# Test1.net
KiCad netlist of a schematic drawn in Altium Designer
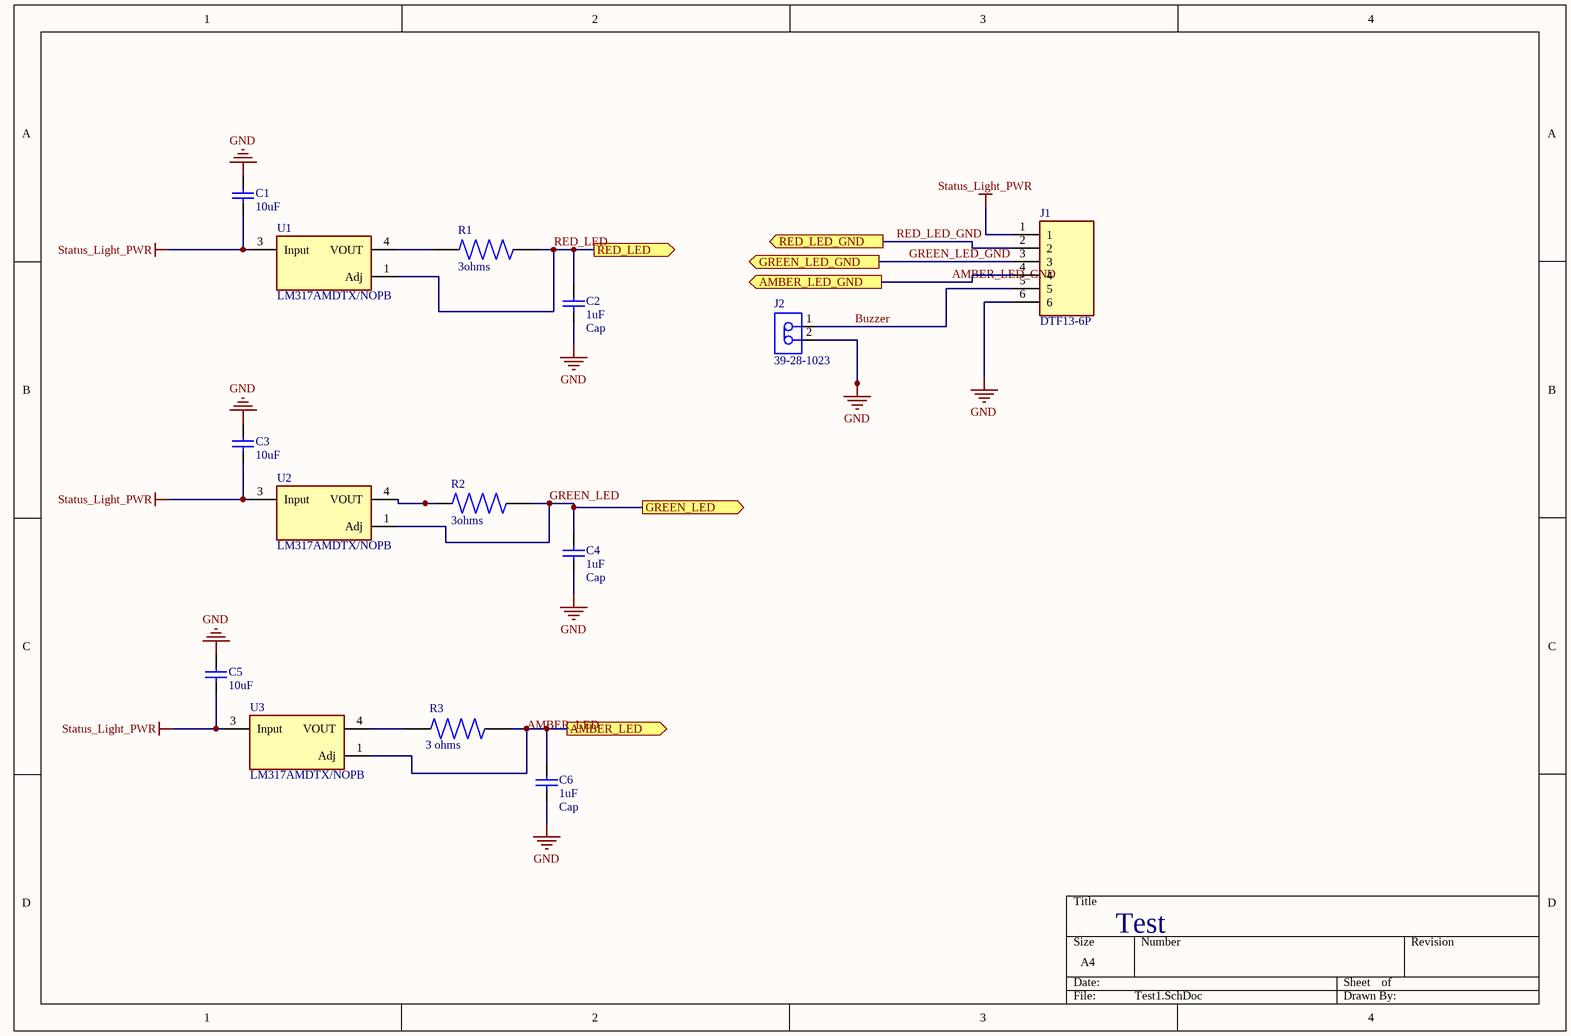
[diagram p0: Test1.SchDoc]

(export (version "E")
  (design (tool "Eeschema 10.0.6"))
  (components
    (comp (ref "C1")
      (value "Cap")
      (footprint "1608[0603]")
      (description "Capacitor")
      (fields (field (name "C2") "10uF") (field (name "PUBLISHER") "Altium Limited"))
      (libsource (lib "Miscellaneous Devices") (part "Cap"))
    )
    (comp (ref "C2")
      (value "Cap")
      (footprint "1608[0603]")
      (description "Capacitor")
      (fields (field (name "C2") "1uF") (field (name "PUBLISHER") "Altium Limited"))
      (libsource (lib "Miscellaneous Devices") (part "Cap"))
    )
    (comp (ref "C3")
      (value "Cap")
      (footprint "1608[0603]")
      (description "Capacitor")
      (fields (field (name "C2") "10uF") (field (name "PUBLISHER") "Altium Limited"))
      (libsource (lib "Miscellaneous Devices") (part "Cap"))
    )
    (comp (ref "C4")
      (value "Cap")
      (footprint "1608[0603]")
      (description "Capacitor")
      (fields (field (name "C2") "1uF") (field (name "PUBLISHER") "Altium Limited"))
      (libsource (lib "Miscellaneous Devices") (part "Cap"))
    )
    (comp (ref "C5")
      (value "Cap")
      (footprint "1608[0603]")
      (description "Capacitor")
      (fields (field (name "C2") "10uF") (field (name "PUBLISHER") "Altium Limited"))
      (libsource (lib "Miscellaneous Devices") (part "Cap"))
    )
    (comp (ref "C6")
      (value "Cap")
      (footprint "1608[0603]")
      (description "Capacitor")
      (fields (field (name "C2") "1uF") (field (name "PUBLISHER") "Altium Limited"))
      (libsource (lib "Miscellaneous Devices") (part "Cap"))
    )
    (comp (ref "J1")
      (value "DTF13-6P")
      (footprint "TE_DTF13-6P")
      (description "Conn Wire to Board RCP 6 POS 4.45mm Solder RA Thru-Hole Automotive Package")
      (fields (field (name "MF") "TE Connectivity"))
      (libsource (lib "DTF13-6P") (part "DTF13-6P"))
    )
    (comp (ref "J2")
      (value "39-28-1023")
      (footprint "MOLX-39-28-1023-2_V")
      (fields (field (name "MANUFACTURER") "Molex"))
      (libsource (lib "Altium Content Vault") (part "CN-2P-F-QF2"))
    )
    (comp (ref "R1")
      (value "3ohms")
      (footprint "RESC3216X70N")
      (fields (field (name "MP") "RMCF1206FT3R00"))
      (libsource (lib "RMCF1206FT3R00") (part "RMCF1206FT3R00"))
    )
    (comp (ref "R2")
      (value "3ohms")
      (footprint "RESC3216X70N")
      (fields (field (name "MP") "RMCF1206FT3R00"))
      (libsource (lib "RMCF1206FT3R00") (part "RMCF1206FT3R00"))
    )
    (comp (ref "R3")
      (value "3 ohms")
      (footprint "RESC3216X70N")
      (fields (field (name "MP") "RMCF1206FT3R00"))
      (libsource (lib "RMCF1206FT3R00") (part "RMCF1206FT3R00"))
    )
    (comp (ref "U1")
      (value "LM317AMDTX/NOPB")
      (footprint "FP-NDP0003B-MFG")
      (description "IC REG LIN POS ADJ 1.5A TO252-3")
      (fields
        (field (name "MANUFACTURER") "Texas Instruments")
        (field (name "OCTOPART") "https://octopart.com/lm317amdtx%2Fnopb-texas+instruments-24813637")
      )
      (libsource (lib "Altium Content Vault") (part "f5e461452ecc37898cb4f29636b01e7"))
    )
    (comp (ref "U2")
      (value "LM317AMDTX/NOPB")
      (footprint "FP-NDP0003B-MFG")
      (description "IC REG LIN POS ADJ 1.5A TO252-3")
      (fields
        (field (name "MANUFACTURER") "Texas Instruments")
        (field (name "OCTOPART") "https://octopart.com/lm317amdtx%2Fnopb-texas+instruments-24813637")
      )
      (libsource (lib "Altium Content Vault") (part "f5e461452ecc37898cb4f29636b01e7"))
    )
    (comp (ref "U3")
      (value "LM317AMDTX/NOPB")
      (footprint "FP-NDP0003B-MFG")
      (description "IC REG LIN POS ADJ 1.5A TO252-3")
      (fields
        (field (name "MANUFACTURER") "Texas Instruments")
        (field (name "OCTOPART") "https://octopart.com/lm317amdtx%2Fnopb-texas+instruments-24813637")
      )
      (libsource (lib "Altium Content Vault") (part "f5e461452ecc37898cb4f29636b01e7"))
    )
  )
  (nets
    (net (code "1") (name "/AMBER_LED") (class "Default")
      (node (ref "C6") (pin "2") (pinfunction "2_2") (pintype "passive"))
      (node (ref "R3") (pin "2") (pinfunction "2_2") (pintype "passive"))
      (node (ref "U3") (pin "1") (pinfunction "Adj_1") (pintype "passive"))
    )
    (net (code "2") (name "/AMBER_LED_GND") (class "Default")
      (node (ref "J1") (pin "4") (pinfunction "4_4") (pintype "passive"))
    )
    (net (code "3") (name "/Buzzer") (class "Default")
      (node (ref "J1") (pin "5") (pinfunction "5_5") (pintype "passive"))
      (node (ref "J2") (pin "1") (pinfunction "1_1") (pintype "passive"))
    )
    (net (code "4") (name "/GREEN_LED") (class "Default")
      (node (ref "C4") (pin "2") (pinfunction "2_2") (pintype "passive"))
      (node (ref "R2") (pin "2") (pinfunction "2_2") (pintype "passive"))
      (node (ref "U2") (pin "1") (pinfunction "Adj_1") (pintype "passive"))
    )
    (net (code "5") (name "/GREEN_LED_GND") (class "Default")
      (node (ref "J1") (pin "3") (pinfunction "3_3") (pintype "passive"))
    )
    (net (code "6") (name "/RED_LED") (class "Default")
      (node (ref "C2") (pin "2") (pinfunction "2_2") (pintype "passive"))
      (node (ref "R1") (pin "2") (pinfunction "2_2") (pintype "passive"))
      (node (ref "U1") (pin "1") (pinfunction "Adj_1") (pintype "passive"))
    )
    (net (code "7") (name "/RED_LED_GND") (class "Default")
      (node (ref "J1") (pin "2") (pinfunction "2_2") (pintype "passive"))
    )
    (net (code "8") (name "GND") (class "Default")
      (node (ref "C1") (pin "2") (pinfunction "2_2") (pintype "passive"))
      (node (ref "C2") (pin "1") (pinfunction "1_1") (pintype "passive"))
      (node (ref "C3") (pin "2") (pinfunction "2_2") (pintype "passive"))
      (node (ref "C4") (pin "1") (pinfunction "1_1") (pintype "passive"))
      (node (ref "C5") (pin "2") (pinfunction "2_2") (pintype "passive"))
      (node (ref "C6") (pin "1") (pinfunction "1_1") (pintype "passive"))
      (node (ref "J1") (pin "6") (pinfunction "6_6") (pintype "passive"))
      (node (ref "J2") (pin "2") (pinfunction "2_2") (pintype "passive"))
    )
    (net (code "9") (name "Net-(U1-VOUT)") (class "Default")
      (node (ref "R1") (pin "1") (pinfunction "1_1") (pintype "passive"))
      (node (ref "U1") (pin "4") (pinfunction "VOUT_4") (pintype "power_in"))
    )
    (net (code "10") (name "Net-(U2-VOUT)") (class "Default")
      (node (ref "R2") (pin "1") (pinfunction "1_1") (pintype "passive"))
      (node (ref "U2") (pin "4") (pinfunction "VOUT_4") (pintype "power_in"))
    )
    (net (code "11") (name "Net-(U3-VOUT)") (class "Default")
      (node (ref "R3") (pin "1") (pinfunction "1_1") (pintype "passive"))
      (node (ref "U3") (pin "4") (pinfunction "VOUT_4") (pintype "power_in"))
    )
    (net (code "12") (name "Status_Light_PWR") (class "Default")
      (node (ref "C1") (pin "1") (pinfunction "1_1") (pintype "passive"))
      (node (ref "C3") (pin "1") (pinfunction "1_1") (pintype "passive"))
      (node (ref "C5") (pin "1") (pinfunction "1_1") (pintype "passive"))
      (node (ref "J1") (pin "1") (pinfunction "1_1") (pintype "passive"))
      (node (ref "U1") (pin "3") (pinfunction "Input_3") (pintype "power_in"))
      (node (ref "U2") (pin "3") (pinfunction "Input_3") (pintype "power_in"))
      (node (ref "U3") (pin "3") (pinfunction "Input_3") (pintype "power_in"))
    )
  )
)
